# PWR_PROT.net
KiCad netlist of a schematic drawn in Altium Designer
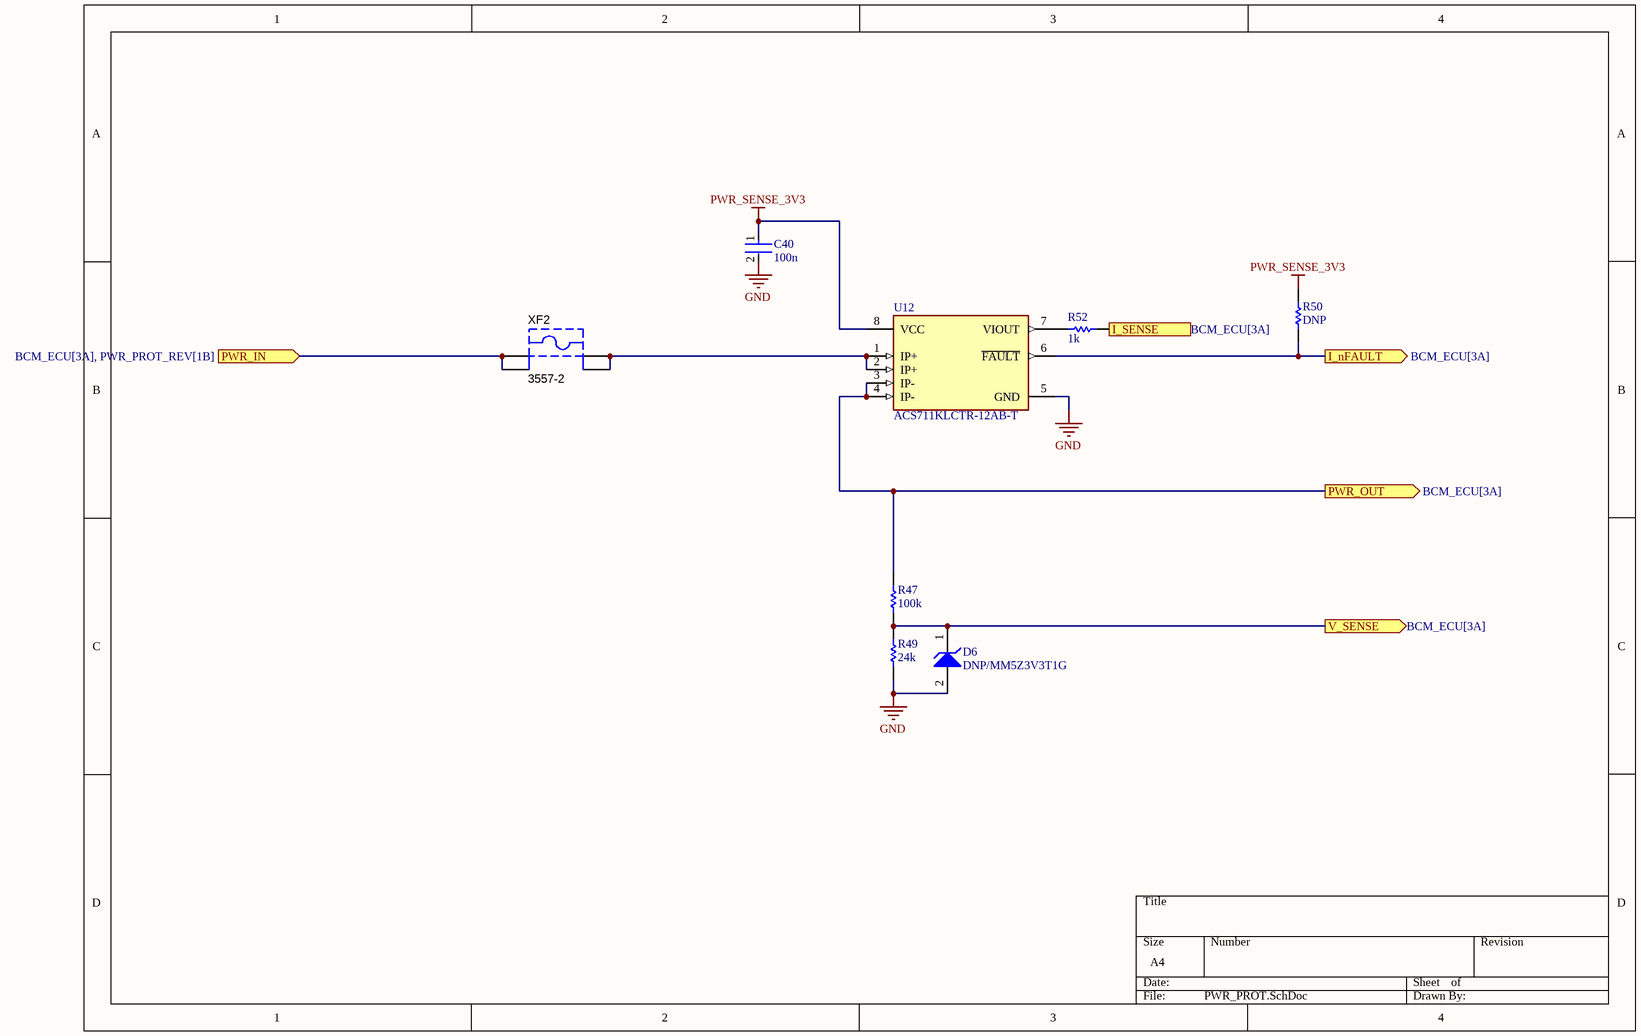
[diagram p0: PWR_PROT.SchDoc]

(export (version "E")
  (design (tool "Eeschema 10.0.6"))
  (components
    (comp (ref "C40")
      (value "100n")
      (footprint "FP-0402-L_1_0_0_05-W_0_5-IPC_A")
      (description "LARGE PADS, 0402 CAP, CHANGE COMMENT TO MATCH REAL P/N")
      (libsource (lib "Space Concordia") (part "b4654b650e69147ec39a6b967a45e02"))
    )
    (comp (ref "D6")
      (value "DNP/MM5Z3V3T1G")
      (footprint "ONSC-SOD-523-2-502-01_V")
      (description "Zener Voltage Regulator, 500 mW, 2-Pin SOD-523, Pb-Free, Tape and Reel")
      (fields (field (name "MANUFACTURER") "On Semiconductor") (field (name "PARTNUMBER") "MM5Z3V3T1G"))
      (libsource (lib "Altium Content Vault") (part "ONSC-K1A2-2"))
    )
    (comp (ref "R47")
      (value "100k")
      (footprint "R0603B")
      (description "Resistor")
      (libsource (lib "Space Concordia") (part "Resistor"))
    )
    (comp (ref "R49")
      (value "24k")
      (footprint "R0603B")
      (description "Resistor")
      (libsource (lib "Space Concordia") (part "Resistor"))
    )
    (comp (ref "R50")
      (value "DNP")
      (footprint "R0603B")
      (description "Resistor")
      (libsource (lib "Space Concordia") (part "Resistor"))
    )
    (comp (ref "R52")
      (value "1k")
      (footprint "R0603B")
      (description "Resistor")
      (libsource (lib "Space Concordia") (part "Resistor"))
    )
    (comp (ref "U12")
      (value "ACS711KLCTR-12AB-T")
      (footprint "FP-LC-8-IPC_C")
      (description "SENSOR CURRENT HALL 12.5A AC/DC")
      (libsource (lib "Altium Content Vault") (part "b5e82308d4912bad35d89a98a7a92f9"))
    )
    (comp (ref "XF2")
      (value "3557-2")
      (footprint "KSTN-3557-2")
      (description "FUSE HOLDER, PCB MOUNT, 500VAC, 20A, ROHS")
      (fields (field (name "VOLTAGE") "500V") (field (name "MANUFACTURER") "Keystone-Electronics"))
      (libsource (lib "Altium Content Vault") (part "FUSE_HOLDER-4"))
    )
  )
  (nets
    (net (code "1") (name "/I_SENSE") (class "Default")
      (node (ref "R52") (pin "1") (pinfunction "1_1") (pintype "passive"))
    )
    (net (code "2") (name "/I_nFAULT") (class "Default")
      (node (ref "R50") (pin "2") (pinfunction "2_2") (pintype "passive"))
      (node (ref "U12") (pin "6") (pinfunction "~{FAULT}_6") (pintype "output"))
    )
    (net (code "3") (name "/PWR_IN") (class "Default")
      (node (ref "XF2") (pin "1") (pinfunction "1_1") (pintype "passive"))
      (node (ref "XF2") (pin "2") (pinfunction "2_2") (pintype "passive"))
    )
    (net (code "4") (name "/PWR_OUT") (class "Default")
      (node (ref "R47") (pin "1") (pinfunction "1_1") (pintype "passive"))
      (node (ref "U12") (pin "3") (pinfunction "IP-_3") (pintype "input"))
      (node (ref "U12") (pin "4") (pinfunction "IP-_4") (pintype "input"))
    )
    (net (code "5") (name "/V_SENSE") (class "Default")
      (node (ref "D6") (pin "1") (pinfunction "K_1") (pintype "passive"))
      (node (ref "R47") (pin "2") (pinfunction "2_2") (pintype "passive"))
      (node (ref "R49") (pin "1") (pinfunction "1_1") (pintype "passive"))
    )
    (net (code "6") (name "GND") (class "Default")
      (node (ref "C40") (pin "2") (pinfunction "2_2") (pintype "passive"))
      (node (ref "D6") (pin "2") (pinfunction "A_2") (pintype "passive"))
      (node (ref "R49") (pin "2") (pinfunction "2_2") (pintype "passive"))
      (node (ref "U12") (pin "5") (pinfunction "GND_5") (pintype "power_in"))
    )
    (net (code "7") (name "Net-(U12-IP+-Pad1)") (class "Default")
      (node (ref "U12") (pin "1") (pinfunction "IP+_1") (pintype "input"))
      (node (ref "U12") (pin "2") (pinfunction "IP+_2") (pintype "input"))
      (node (ref "XF2") (pin "3") (pinfunction "3_3") (pintype "passive"))
      (node (ref "XF2") (pin "4") (pinfunction "4_4") (pintype "passive"))
    )
    (net (code "8") (name "Net-(U12-VIOUT)") (class "Default")
      (node (ref "R52") (pin "2") (pinfunction "2_2") (pintype "passive"))
      (node (ref "U12") (pin "7") (pinfunction "VIOUT_7") (pintype "output"))
    )
    (net (code "9") (name "PWR_SENSE_3V3") (class "Default")
      (node (ref "C40") (pin "1") (pinfunction "1_1") (pintype "passive"))
      (node (ref "R50") (pin "1") (pinfunction "1_1") (pintype "passive"))
      (node (ref "U12") (pin "8") (pinfunction "VCC_8") (pintype "power_in"))
    )
  )
)
